# mic.net
KiCad netlist of a schematic drawn in Altium Designer
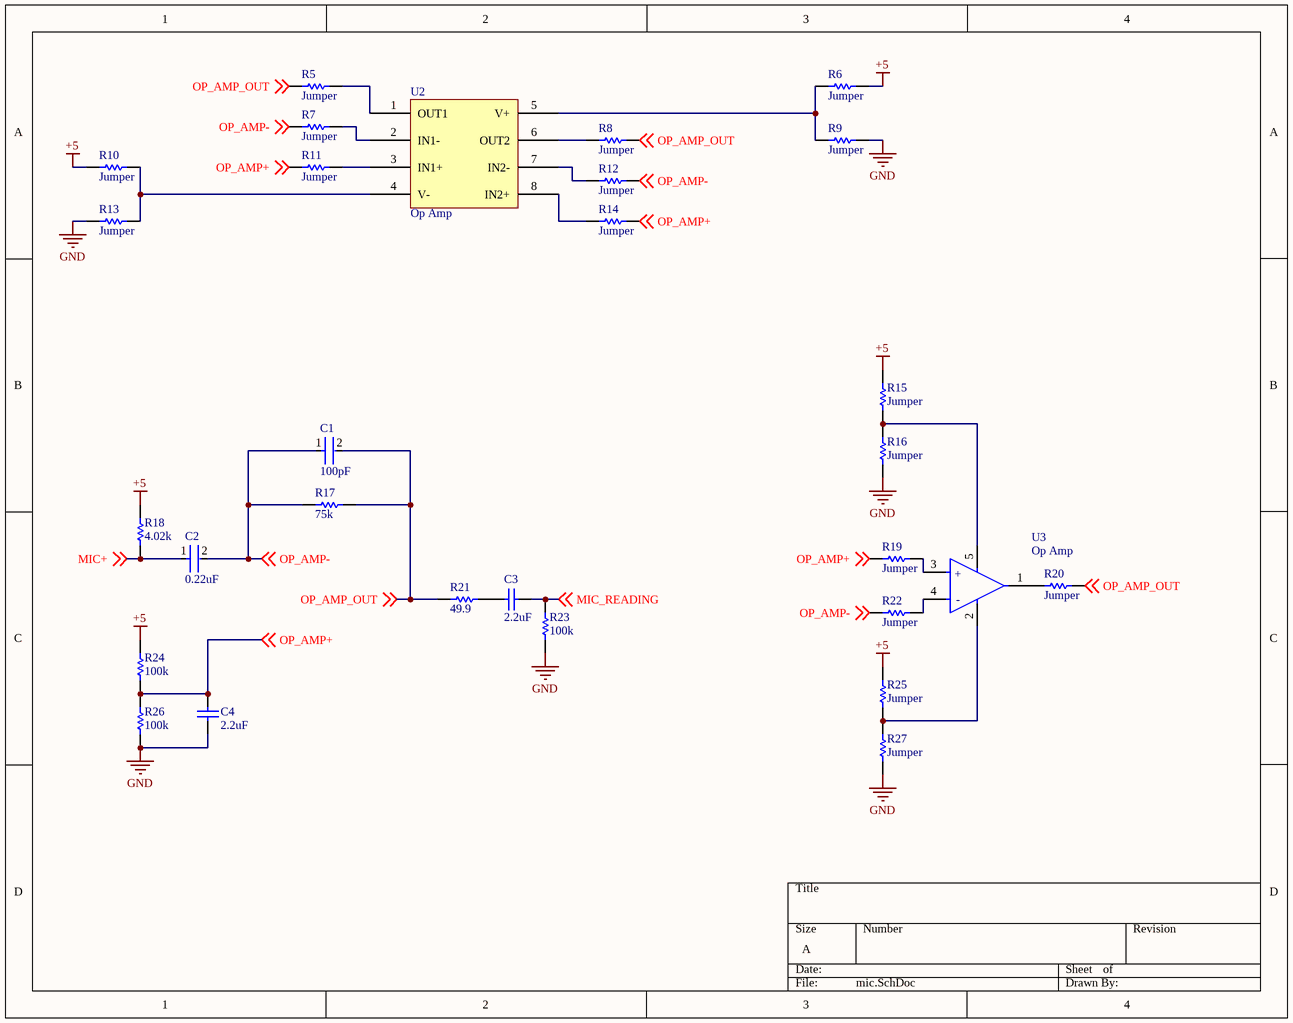
[diagram p0: mic.SchDoc]

(export (version "E")
  (design (tool "Eeschema 10.0.6"))
  (components
    (comp (ref "C1")
      (value "100pF")
      (footprint "FP-C0805C-DN-MFG")
      (description "C0805 100 pF C0G 30ppm/°C 5.00% 50 V")
      (fields (field (name "OCTOPART") "https://octopart.com/c0805c101j5gactu-kemet-100795"))
      (libsource (lib "Altium Content Vault") (part "b4654b650e69147ec39a6b967a45e02"))
    )
    (comp (ref "C2")
      (value "0.22uF")
      (footprint "FP-C0805C-DN-MFG")
      (description "C0805 0.22 μF X7R 30ppm/°C 10.00% 50 V")
      (fields (field (name "MANUFACTURER") "KEMET"))
      (libsource (lib "Altium Content Vault") (part "b4654b650e69147ec39a6b967a45e02"))
    )
    (comp (ref "C3")
      (value "2.2uF")
      (footprint "CAPC2113X140X50LL30T25")
      (fields (field (name "PART NUMBER") "C0805C225K8RACTU") (field (name "MANUFACTURER") "Kemet"))
      (libsource (lib "Altium Content Vault") (part "CAP"))
    )
    (comp (ref "C4")
      (value "2.2uF")
      (footprint "CAPC2113X140X50LL30T25")
      (fields (field (name "PART NUMBER") "C0805C225K8RACTU") (field (name "MANUFACTURER") "Kemet"))
      (libsource (lib "Altium Content Vault") (part "CAP"))
    )
    (comp (ref "R5")
      (value "Jumper")
      (footprint "RESC2013X70X40NL20T20")
      (description "Chip Resistor, 0 Ohm, +/- 1%, 0.125 W, -55 to 155 degC, 0805 (2012 Metric), RoHS, Tape and Reel")
      (fields (field (name "PARTNUMBER") "ERJ-6GEY0R00V") (field (name "TOLERANCE") "5%"))
      (libsource (lib "Altium Content Vault") (part "RES-2"))
    )
    (comp (ref "R6")
      (value "Jumper")
      (footprint "RESC2013X70X40NL20T20")
      (description "Chip Resistor, 0 Ohm, +/- 1%, 0.125 W, -55 to 155 degC, 0805 (2012 Metric), RoHS, Tape and Reel")
      (fields (field (name "PARTNUMBER") "ERJ-6GEY0R00V") (field (name "TOLERANCE") "5%"))
      (libsource (lib "Altium Content Vault") (part "RES-2"))
    )
    (comp (ref "R7")
      (value "Jumper")
      (footprint "RESC2013X70X40NL20T20")
      (description "Chip Resistor, 0 Ohm, +/- 1%, 0.125 W, -55 to 155 degC, 0805 (2012 Metric), RoHS, Tape and Reel")
      (fields (field (name "PARTNUMBER") "ERJ-6GEY0R00V") (field (name "TOLERANCE") "5%"))
      (libsource (lib "Altium Content Vault") (part "RES-2"))
    )
    (comp (ref "R8")
      (value "Jumper")
      (footprint "RESC2013X70X40NL20T20")
      (description "Chip Resistor, 0 Ohm, +/- 1%, 0.125 W, -55 to 155 degC, 0805 (2012 Metric), RoHS, Tape and Reel")
      (fields (field (name "PARTNUMBER") "ERJ-6GEY0R00V") (field (name "TOLERANCE") "5%"))
      (libsource (lib "Altium Content Vault") (part "RES-2"))
    )
    (comp (ref "R9")
      (value "Jumper")
      (footprint "RESC2013X70X40NL20T20")
      (description "Chip Resistor, 0 Ohm, +/- 1%, 0.125 W, -55 to 155 degC, 0805 (2012 Metric), RoHS, Tape and Reel")
      (fields (field (name "PARTNUMBER") "ERJ-6GEY0R00V") (field (name "TOLERANCE") "5%"))
      (libsource (lib "Altium Content Vault") (part "RES-2"))
    )
    (comp (ref "R10")
      (value "Jumper")
      (footprint "RESC2013X70X40NL20T20")
      (description "Chip Resistor, 0 Ohm, +/- 1%, 0.125 W, -55 to 155 degC, 0805 (2012 Metric), RoHS, Tape and Reel")
      (fields (field (name "PARTNUMBER") "ERJ-6GEY0R00V") (field (name "TOLERANCE") "5%"))
      (libsource (lib "Altium Content Vault") (part "RES-2"))
    )
    (comp (ref "R11")
      (value "Jumper")
      (footprint "RESC2013X70X40NL20T20")
      (description "Chip Resistor, 0 Ohm, +/- 1%, 0.125 W, -55 to 155 degC, 0805 (2012 Metric), RoHS, Tape and Reel")
      (fields (field (name "PARTNUMBER") "ERJ-6GEY0R00V") (field (name "TOLERANCE") "5%"))
      (libsource (lib "Altium Content Vault") (part "RES-2"))
    )
    (comp (ref "R12")
      (value "Jumper")
      (footprint "RESC2013X70X40NL20T20")
      (description "Chip Resistor, 0 Ohm, +/- 1%, 0.125 W, -55 to 155 degC, 0805 (2012 Metric), RoHS, Tape and Reel")
      (fields (field (name "PARTNUMBER") "ERJ-6GEY0R00V") (field (name "TOLERANCE") "5%"))
      (libsource (lib "Altium Content Vault") (part "RES-2"))
    )
    (comp (ref "R13")
      (value "Jumper")
      (footprint "RESC2013X70X40NL20T20")
      (description "Chip Resistor, 0 Ohm, +/- 1%, 0.125 W, -55 to 155 degC, 0805 (2012 Metric), RoHS, Tape and Reel")
      (fields (field (name "PARTNUMBER") "ERJ-6GEY0R00V") (field (name "TOLERANCE") "5%"))
      (libsource (lib "Altium Content Vault") (part "RES-2"))
    )
    (comp (ref "R14")
      (value "Jumper")
      (footprint "RESC2013X70X40NL20T20")
      (description "Chip Resistor, 0 Ohm, +/- 1%, 0.125 W, -55 to 155 degC, 0805 (2012 Metric), RoHS, Tape and Reel")
      (fields (field (name "PARTNUMBER") "ERJ-6GEY0R00V") (field (name "TOLERANCE") "5%"))
      (libsource (lib "Altium Content Vault") (part "RES-2"))
    )
    (comp (ref "R15")
      (value "Jumper")
      (footprint "RESC2013X70X40NL20T20")
      (description "Chip Resistor, 0 Ohm, +/- 1%, 0.125 W, -55 to 155 degC, 0805 (2012 Metric), RoHS, Tape and Reel")
      (fields (field (name "PARTNUMBER") "ERJ-6GEY0R00V") (field (name "TOLERANCE") "5%"))
      (libsource (lib "Altium Content Vault") (part "RES-2"))
    )
    (comp (ref "R16")
      (value "Jumper")
      (footprint "RESC2013X70X40NL20T20")
      (description "Chip Resistor, 0 Ohm, +/- 1%, 0.125 W, -55 to 155 degC, 0805 (2012 Metric), RoHS, Tape and Reel")
      (fields (field (name "PARTNUMBER") "ERJ-6GEY0R00V") (field (name "TOLERANCE") "5%"))
      (libsource (lib "Altium Content Vault") (part "RES-2"))
    )
    (comp (ref "R17")
      (value "75k")
      (footprint "RESC2013X70X40NL20T20")
      (fields (field (name "PART NUMBER") "ERJ-6ENF7502V") (field (name "MANUFACTURER") "Panasonic"))
      (libsource (lib "Altium Content Vault") (part "RES"))
    )
    (comp (ref "R18")
      (value "4.02k")
      (footprint "RESC2013X70X40NL20T20")
      (fields (field (name "PART NUMBER") "ERJ-6ENF4021V") (field (name "MANUFACTURER") "Panasonic"))
      (libsource (lib "Altium Content Vault") (part "RES"))
    )
    (comp (ref "R19")
      (value "Jumper")
      (footprint "RESC2013X70X40NL20T20")
      (description "Chip Resistor, 0 Ohm, +/- 1%, 0.125 W, -55 to 155 degC, 0805 (2012 Metric), RoHS, Tape and Reel")
      (fields (field (name "PARTNUMBER") "ERJ-6GEY0R00V") (field (name "TOLERANCE") "5%"))
      (libsource (lib "Altium Content Vault") (part "RES-2"))
    )
    (comp (ref "R20")
      (value "Jumper")
      (footprint "RESC2013X70X40NL20T20")
      (description "Chip Resistor, 0 Ohm, +/- 1%, 0.125 W, -55 to 155 degC, 0805 (2012 Metric), RoHS, Tape and Reel")
      (fields (field (name "PARTNUMBER") "ERJ-6GEY0R00V") (field (name "TOLERANCE") "5%"))
      (libsource (lib "Altium Content Vault") (part "RES-2"))
    )
    (comp (ref "R21")
      (value "49.9")
      (footprint "RESC2013X70X40NL20T20")
      (fields (field (name "PART NUMBER") "ERJ-6ENF49R9V") (field (name "MANUFACTURER") "Panasonic"))
      (libsource (lib "Altium Content Vault") (part "RES"))
    )
    (comp (ref "R22")
      (value "Jumper")
      (footprint "RESC2013X70X40NL20T20")
      (description "Chip Resistor, 0 Ohm, +/- 1%, 0.125 W, -55 to 155 degC, 0805 (2012 Metric), RoHS, Tape and Reel")
      (fields (field (name "PARTNUMBER") "ERJ-6GEY0R00V") (field (name "TOLERANCE") "5%"))
      (libsource (lib "Altium Content Vault") (part "RES-2"))
    )
    (comp (ref "R23")
      (value "100k")
      (footprint "RESC2013X70X40ML20T20")
      (fields (field (name "PART NUMBER") "ERJ-6ENF1003V") (field (name "MANUFACTURER") "Panasonic"))
      (libsource (lib "Altium Content Vault") (part "RES"))
    )
    (comp (ref "R24")
      (value "100k")
      (footprint "RESC2013X70X40ML20T20")
      (fields (field (name "PART NUMBER") "ERJ-6ENF1003V") (field (name "MANUFACTURER") "Panasonic"))
      (libsource (lib "Altium Content Vault") (part "RES"))
    )
    (comp (ref "R25")
      (value "Jumper")
      (footprint "RESC2013X70X40NL20T20")
      (description "Chip Resistor, 0 Ohm, +/- 1%, 0.125 W, -55 to 155 degC, 0805 (2012 Metric), RoHS, Tape and Reel")
      (fields (field (name "PARTNUMBER") "ERJ-6GEY0R00V") (field (name "TOLERANCE") "5%"))
      (libsource (lib "Altium Content Vault") (part "RES-2"))
    )
    (comp (ref "R26")
      (value "100k")
      (footprint "RESC2013X70X40ML20T20")
      (fields (field (name "PART NUMBER") "ERJ-6ENF1003V") (field (name "MANUFACTURER") "Panasonic"))
      (libsource (lib "Altium Content Vault") (part "RES"))
    )
    (comp (ref "R27")
      (value "Jumper")
      (footprint "RESC2013X70X40NL20T20")
      (description "Chip Resistor, 0 Ohm, +/- 1%, 0.125 W, -55 to 155 degC, 0805 (2012 Metric), RoHS, Tape and Reel")
      (fields (field (name "PARTNUMBER") "ERJ-6GEY0R00V") (field (name "TOLERANCE") "5%"))
      (libsource (lib "Altium Content Vault") (part "RES-2"))
    )
    (comp (ref "U2") (value "Op Amp") (footprint "Op Amp") (libsource (lib "3400 Sch Lib") (part "Op Amp")))
    (comp (ref "U3")
      (value "Op Amp")
      (footprint "FP-DBV0005A-MFG")
      (description "IC OPAMP GP 1 CIRCUIT SOT23-5")
      (fields (field (name "MPN") "OPA172IDBVT"))
      (libsource (lib "Altium Content Vault") (part "1dcd28e651784f0a5a8ed6f8452eeff"))
    )
  )
  (nets
    (net (code "1") (name "+5") (class "Default")
      (node (ref "R10") (pin "1") (pinfunction "1_1") (pintype "passive"))
      (node (ref "R15") (pin "1") (pinfunction "1_1") (pintype "passive"))
      (node (ref "R18") (pin "2") (pinfunction "2_2") (pintype "passive"))
      (node (ref "R24") (pin "2") (pinfunction "2_2") (pintype "passive"))
      (node (ref "R25") (pin "1") (pinfunction "1_1") (pintype "passive"))
      (node (ref "R6") (pin "2") (pinfunction "2_2") (pintype "passive"))
    )
    (net (code "2") (name "GND") (class "Default")
      (node (ref "C4") (pin "1") (pinfunction "1_1") (pintype "passive"))
      (node (ref "R13") (pin "1") (pinfunction "1_1") (pintype "passive"))
      (node (ref "R16") (pin "2") (pinfunction "2_2") (pintype "passive"))
      (node (ref "R23") (pin "1") (pinfunction "1_1") (pintype "passive"))
      (node (ref "R26") (pin "1") (pinfunction "1_1") (pintype "passive"))
      (node (ref "R27") (pin "2") (pinfunction "2_2") (pintype "passive"))
      (node (ref "R9") (pin "2") (pinfunction "2_2") (pintype "passive"))
    )
    (net (code "3") (name "MIC+") (class "Default")
      (node (ref "C2") (pin "1") (pinfunction "1_1") (pintype "passive"))
      (node (ref "R18") (pin "1") (pinfunction "1_1") (pintype "passive"))
    )
    (net (code "4") (name "MIC_READING") (class "Default")
      (node (ref "C3") (pin "1") (pinfunction "1_1") (pintype "passive"))
      (node (ref "R23") (pin "2") (pinfunction "2_2") (pintype "passive"))
    )
    (net (code "5") (name "Net-(C3-Pad2)") (class "Default")
      (node (ref "C3") (pin "2") (pinfunction "2_2") (pintype "passive"))
      (node (ref "R21") (pin "1") (pinfunction "1_1") (pintype "passive"))
    )
    (net (code "6") (name "Net-(U2-IN1+)") (class "Default")
      (node (ref "R11") (pin "2") (pinfunction "2_2") (pintype "passive"))
      (node (ref "U2") (pin "3") (pinfunction "IN1+_3") (pintype "passive"))
    )
    (net (code "7") (name "Net-(U2-IN1-)") (class "Default")
      (node (ref "R7") (pin "2") (pinfunction "2_2") (pintype "passive"))
      (node (ref "U2") (pin "2") (pinfunction "IN1-_2") (pintype "passive"))
    )
    (net (code "8") (name "Net-(U2-IN2+)") (class "Default")
      (node (ref "R14") (pin "1") (pinfunction "1_1") (pintype "passive"))
      (node (ref "U2") (pin "8") (pinfunction "IN2+_8") (pintype "passive"))
    )
    (net (code "9") (name "Net-(U2-IN2-)") (class "Default")
      (node (ref "R12") (pin "1") (pinfunction "1_1") (pintype "passive"))
      (node (ref "U2") (pin "7") (pinfunction "IN2-_7") (pintype "passive"))
    )
    (net (code "10") (name "Net-(U2-OUT1)") (class "Default")
      (node (ref "R5") (pin "2") (pinfunction "2_2") (pintype "passive"))
      (node (ref "U2") (pin "1") (pinfunction "OUT1_1") (pintype "passive"))
    )
    (net (code "11") (name "Net-(U2-OUT2)") (class "Default")
      (node (ref "R8") (pin "1") (pinfunction "1_1") (pintype "passive"))
      (node (ref "U2") (pin "6") (pinfunction "OUT2_6") (pintype "passive"))
    )
    (net (code "12") (name "Net-(U2-V+)") (class "Default")
      (node (ref "R6") (pin "1") (pinfunction "1_1") (pintype "passive"))
      (node (ref "R9") (pin "1") (pinfunction "1_1") (pintype "passive"))
      (node (ref "U2") (pin "5") (pinfunction "V+_5") (pintype "passive"))
    )
    (net (code "13") (name "Net-(U2-V-)") (class "Default")
      (node (ref "R10") (pin "2") (pinfunction "2_2") (pintype "passive"))
      (node (ref "R13") (pin "2") (pinfunction "2_2") (pintype "passive"))
      (node (ref "U2") (pin "4") (pinfunction "V-_4") (pintype "passive"))
    )
    (net (code "14") (name "Net-(U3-+IN)") (class "Default")
      (node (ref "R19") (pin "2") (pinfunction "2_2") (pintype "passive"))
      (node (ref "U3") (pin "3") (pinfunction "+IN_3") (pintype "tri_state"))
    )
    (net (code "15") (name "Net-(U3--IN)") (class "Default")
      (node (ref "R22") (pin "2") (pinfunction "2_2") (pintype "passive"))
      (node (ref "U3") (pin "4") (pinfunction "-IN_4") (pintype "tri_state"))
    )
    (net (code "16") (name "Net-(U3-OUT)") (class "Default")
      (node (ref "R20") (pin "1") (pinfunction "1_1") (pintype "passive"))
      (node (ref "U3") (pin "1") (pinfunction "OUT_1") (pintype "passive"))
    )
    (net (code "17") (name "Net-(U3-V+)") (class "Default")
      (node (ref "R15") (pin "2") (pinfunction "2_2") (pintype "passive"))
      (node (ref "R16") (pin "1") (pinfunction "1_1") (pintype "passive"))
      (node (ref "U3") (pin "5") (pinfunction "V+_5") (pintype "passive"))
    )
    (net (code "18") (name "Net-(U3-V-)") (class "Default")
      (node (ref "R25") (pin "2") (pinfunction "2_2") (pintype "passive"))
      (node (ref "R27") (pin "1") (pinfunction "1_1") (pintype "passive"))
      (node (ref "U3") (pin "2") (pinfunction "V-_2") (pintype "power_in"))
    )
    (net (code "19") (name "OP_AMP+") (class "Default")
      (node (ref "C4") (pin "2") (pinfunction "2_2") (pintype "passive"))
      (node (ref "R11") (pin "1") (pinfunction "1_1") (pintype "passive"))
      (node (ref "R14") (pin "2") (pinfunction "2_2") (pintype "passive"))
      (node (ref "R19") (pin "1") (pinfunction "1_1") (pintype "passive"))
      (node (ref "R24") (pin "1") (pinfunction "1_1") (pintype "passive"))
      (node (ref "R26") (pin "2") (pinfunction "2_2") (pintype "passive"))
    )
    (net (code "20") (name "OP_AMP-") (class "Default")
      (node (ref "C1") (pin "1") (pinfunction "1_1") (pintype "passive"))
      (node (ref "C2") (pin "2") (pinfunction "2_2") (pintype "passive"))
      (node (ref "R12") (pin "2") (pinfunction "2_2") (pintype "passive"))
      (node (ref "R17") (pin "2") (pinfunction "2_2") (pintype "passive"))
      (node (ref "R22") (pin "1") (pinfunction "1_1") (pintype "passive"))
      (node (ref "R7") (pin "1") (pinfunction "1_1") (pintype "passive"))
    )
    (net (code "21") (name "OP_AMP_OUT") (class "Default")
      (node (ref "C1") (pin "2") (pinfunction "2_2") (pintype "passive"))
      (node (ref "R17") (pin "1") (pinfunction "1_1") (pintype "passive"))
      (node (ref "R20") (pin "2") (pinfunction "2_2") (pintype "passive"))
      (node (ref "R21") (pin "2") (pinfunction "2_2") (pintype "passive"))
      (node (ref "R5") (pin "1") (pinfunction "1_1") (pintype "passive"))
      (node (ref "R8") (pin "2") (pinfunction "2_2") (pintype "passive"))
    )
  )
)
